# Sens_BMP085.net
KiCad netlist of a schematic drawn in EAGLE
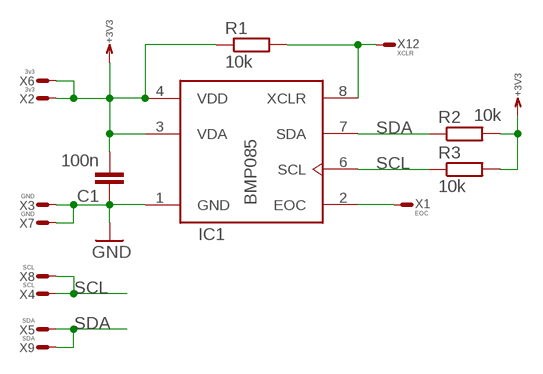
[diagram p0: schematic, sheet 1]

(export (version "E")
  (design (tool "Eeschema 10.0.6"))
  (components
    (comp (ref "C1")
      (value "100n")
      (footprint "eagle-import:0603")
      (libsource (lib "eagle-import") (part "C0603"))
    )
    (comp (ref "IC1")
      (value "BMP085")
      (footprint "eagle-import:LCC8")
      (libsource (lib "eagle-import") (part "BMP085"))
    )
    (comp (ref "R1")
      (value "10k")
      (footprint "eagle-import:0603")
      (libsource (lib "eagle-import") (part "R0603"))
    )
    (comp (ref "R2")
      (value "10k")
      (footprint "eagle-import:0603")
      (libsource (lib "eagle-import") (part "R0603"))
    )
    (comp (ref "R3")
      (value "10k")
      (footprint "eagle-import:0603")
      (libsource (lib "eagle-import") (part "R0603"))
    )
    (comp (ref "X1")
      (value "EOC")
      (footprint "eagle-import:S1.27R")
      (libsource (lib "eagle-import") (part "WIREPADR"))
    )
    (comp (ref "X2")
      (value "3v3")
      (footprint "eagle-import:T1.6_0.9")
      (libsource (lib "eagle-import") (part "WIREPADT1.6/0.9"))
    )
    (comp (ref "X3")
      (value "GND")
      (footprint "eagle-import:T1.6_0.9")
      (libsource (lib "eagle-import") (part "WIREPADT1.6/0.9"))
    )
    (comp (ref "X4")
      (value "SCL")
      (footprint "eagle-import:T1.6_0.9")
      (libsource (lib "eagle-import") (part "WIREPADT1.6/0.9"))
    )
    (comp (ref "X5")
      (value "SDA")
      (footprint "eagle-import:T1.6_0.9")
      (libsource (lib "eagle-import") (part "WIREPADT1.6/0.9"))
    )
    (comp (ref "X6")
      (value "3v3")
      (footprint "eagle-import:T1.6_0.9")
      (libsource (lib "eagle-import") (part "WIREPADT1.6/0.9"))
    )
    (comp (ref "X7")
      (value "GND")
      (footprint "eagle-import:T1.6_0.9")
      (libsource (lib "eagle-import") (part "WIREPADT1.6/0.9"))
    )
    (comp (ref "X8")
      (value "SCL")
      (footprint "eagle-import:T1.6_0.9")
      (libsource (lib "eagle-import") (part "WIREPADT1.6/0.9"))
    )
    (comp (ref "X9")
      (value "SDA")
      (footprint "eagle-import:T1.6_0.9")
      (libsource (lib "eagle-import") (part "WIREPADT1.6/0.9"))
    )
    (comp (ref "X12")
      (value "XCLR")
      (footprint "eagle-import:S1.27R")
      (libsource (lib "eagle-import") (part "WIREPADR"))
    )
  )
  (nets
    (net (code "1") (name "+3V3") (class "Default")
      (node (ref "C1") (pin "2") (pinfunction "2_2") (pintype "passive"))
      (node (ref "IC1") (pin "3") (pinfunction "VDA_3") (pintype "input"))
      (node (ref "IC1") (pin "4") (pinfunction "VDD_4") (pintype "input"))
      (node (ref "R1") (pin "1") (pinfunction "1_1") (pintype "passive"))
      (node (ref "R2") (pin "2") (pinfunction "2_2") (pintype "passive"))
      (node (ref "R3") (pin "2") (pinfunction "2_2") (pintype "passive"))
      (node (ref "X2") (pin "1") (pinfunction "S_1") (pintype "passive"))
      (node (ref "X6") (pin "1") (pinfunction "S_1") (pintype "passive"))
    )
    (net (code "2") (name "/SCL") (class "Default")
      (node (ref "IC1") (pin "6") (pinfunction "SCL_6") (pintype "input"))
      (node (ref "R3") (pin "1") (pinfunction "1_1") (pintype "passive"))
      (node (ref "X4") (pin "1") (pinfunction "S_1") (pintype "passive"))
      (node (ref "X8") (pin "1") (pinfunction "S_1") (pintype "passive"))
    )
    (net (code "3") (name "/SDA") (class "Default")
      (node (ref "IC1") (pin "7") (pinfunction "SDA_7") (pintype "bidirectional"))
      (node (ref "R2") (pin "1") (pinfunction "1_1") (pintype "passive"))
      (node (ref "X5") (pin "1") (pinfunction "S_1") (pintype "passive"))
      (node (ref "X9") (pin "1") (pinfunction "S_1") (pintype "passive"))
    )
    (net (code "4") (name "GND") (class "Default")
      (node (ref "C1") (pin "1") (pinfunction "1_1") (pintype "passive"))
      (node (ref "IC1") (pin "1") (pinfunction "GND_1") (pintype "input"))
      (node (ref "X3") (pin "1") (pinfunction "S_1") (pintype "passive"))
      (node (ref "X7") (pin "1") (pinfunction "S_1") (pintype "passive"))
    )
    (net (code "5") (name "Net-(IC1-EOC)") (class "Default")
      (node (ref "IC1") (pin "2") (pinfunction "EOC_2") (pintype "output"))
      (node (ref "X1") (pin "1") (pinfunction "S_1") (pintype "passive"))
    )
    (net (code "6") (name "Net-(IC1-XCLR)") (class "Default")
      (node (ref "IC1") (pin "8") (pinfunction "XCLR_8") (pintype "input"))
      (node (ref "R1") (pin "2") (pinfunction "2_2") (pintype "passive"))
      (node (ref "X12") (pin "1") (pinfunction "S_1") (pintype "passive"))
    )
  )
)
